# Strombegrenzung_RevA.net
KiCad netlist of a schematic drawn in EAGLE
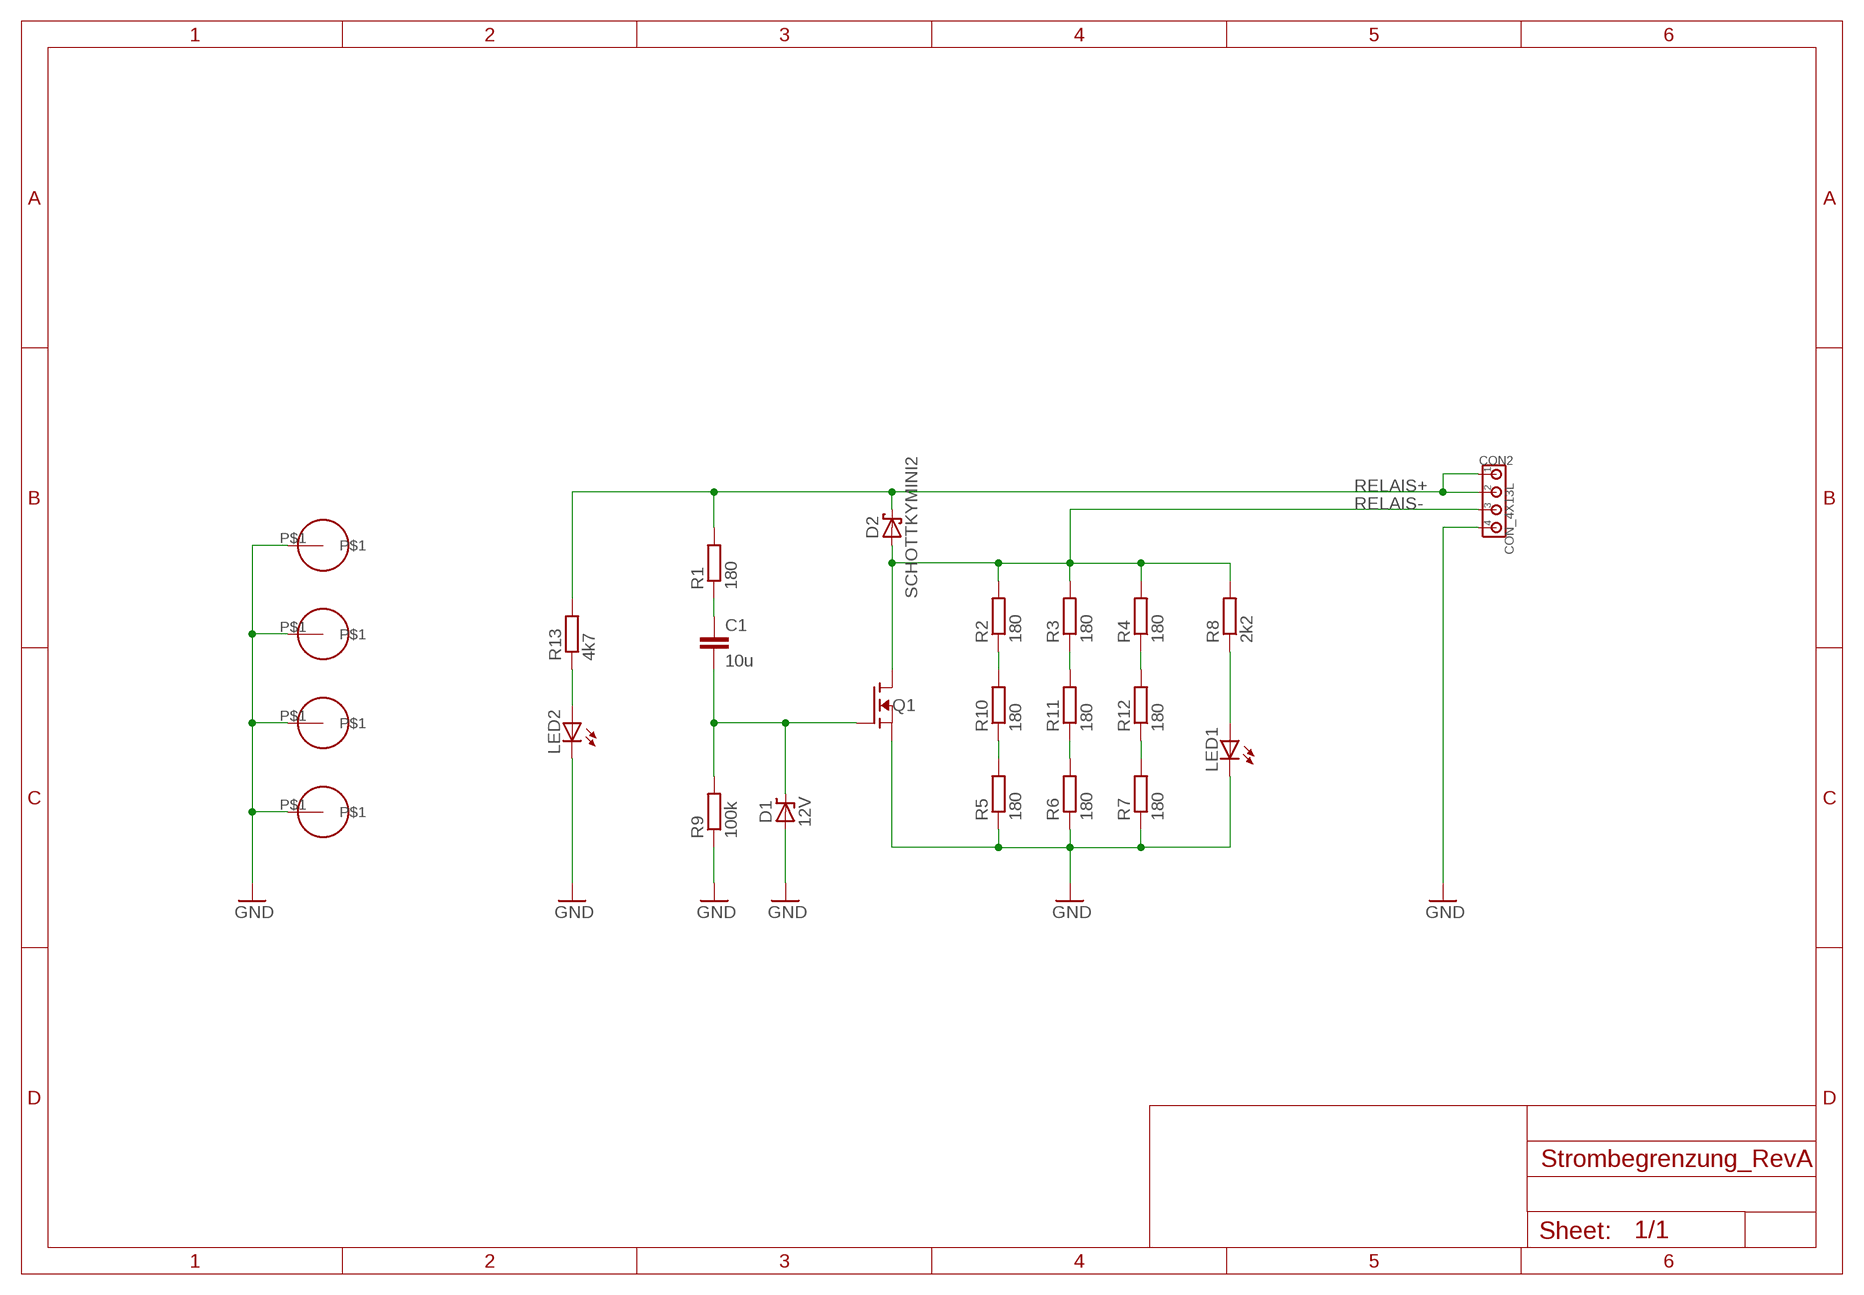
[diagram p0: schematic, sheet 1]

(export (version "E")
  (design (tool "Eeschema 10.0.6"))
  (components
    (comp (ref "C1")
      (value "10u")
      (footprint "eagle-import:C1206")
      (libsource (lib "eagle-import") (part "CC1206"))
    )
    (comp (ref "CON2")
      (value "CON_4X13L")
      (footprint "eagle-import:200MIL_4X")
      (libsource (lib "eagle-import") (part "CON_4X13L"))
    )
    (comp (ref "D1")
      (value "12V")
      (footprint "eagle-import:SOD323")
      (libsource (lib "eagle-import") (part "ZENERSOD323"))
    )
    (comp (ref "D2")
      (value "SCHOTTKYMINI2")
      (footprint "eagle-import:MINI2-F3-B")
      (libsource (lib "eagle-import") (part "SCHOTTKYMINI2"))
    )
    (comp (ref "LED1")
      (value "LED0805")
      (footprint "eagle-import:LED0805")
      (libsource (lib "eagle-import") (part "LED0805"))
    )
    (comp (ref "LED2")
      (value "LED0805")
      (footprint "eagle-import:LED0805")
      (libsource (lib "eagle-import") (part "LED0805"))
    )
    (comp (ref "Q1")
      (value "N-FETSOT23")
      (footprint "eagle-import:SOT23")
      (libsource (lib "eagle-import") (part "N-FETSOT23"))
    )
    (comp (ref "R1")
      (value "180")
      (footprint "eagle-import:R0805")
      (libsource (lib "eagle-import") (part "RESISTORR0805"))
    )
    (comp (ref "R2")
      (value "180")
      (footprint "eagle-import:R0805")
      (libsource (lib "eagle-import") (part "RESISTORR0805"))
    )
    (comp (ref "R3")
      (value "180")
      (footprint "eagle-import:R0805")
      (libsource (lib "eagle-import") (part "RESISTORR0805"))
    )
    (comp (ref "R4")
      (value "180")
      (footprint "eagle-import:R0805")
      (libsource (lib "eagle-import") (part "RESISTORR0805"))
    )
    (comp (ref "R5")
      (value "180")
      (footprint "eagle-import:R0805")
      (libsource (lib "eagle-import") (part "RESISTORR0805"))
    )
    (comp (ref "R6")
      (value "180")
      (footprint "eagle-import:R0805")
      (libsource (lib "eagle-import") (part "RESISTORR0805"))
    )
    (comp (ref "R7")
      (value "180")
      (footprint "eagle-import:R0805")
      (libsource (lib "eagle-import") (part "RESISTORR0805"))
    )
    (comp (ref "R8")
      (value "2k2")
      (footprint "eagle-import:R0805")
      (libsource (lib "eagle-import") (part "RESISTORR0805"))
    )
    (comp (ref "R9")
      (value "100k")
      (footprint "eagle-import:R0805")
      (libsource (lib "eagle-import") (part "RESISTORR0805"))
    )
    (comp (ref "R10")
      (value "180")
      (footprint "eagle-import:R0805")
      (libsource (lib "eagle-import") (part "RESISTORR0805"))
    )
    (comp (ref "R11")
      (value "180")
      (footprint "eagle-import:R0805")
      (libsource (lib "eagle-import") (part "RESISTORR0805"))
    )
    (comp (ref "R12")
      (value "180")
      (footprint "eagle-import:R0805")
      (libsource (lib "eagle-import") (part "RESISTORR0805"))
    )
    (comp (ref "R13")
      (value "4k7")
      (footprint "eagle-import:R0805")
      (libsource (lib "eagle-import") (part "RESISTORR0805"))
    )
    (comp (ref "U$1")
      (value "HOLE_3.3MM")
      (footprint "eagle-import:HOLE_3.3MM")
      (libsource (lib "eagle-import") (part "HOLE_3.3MM"))
    )
    (comp (ref "U$2")
      (value "HOLE_3.3MM")
      (footprint "eagle-import:HOLE_3.3MM")
      (libsource (lib "eagle-import") (part "HOLE_3.3MM"))
    )
    (comp (ref "U$3")
      (value "HOLE_3.3MM")
      (footprint "eagle-import:HOLE_3.3MM")
      (libsource (lib "eagle-import") (part "HOLE_3.3MM"))
    )
    (comp (ref "U$4")
      (value "HOLE_3.3MM")
      (footprint "eagle-import:HOLE_3.3MM")
      (libsource (lib "eagle-import") (part "HOLE_3.3MM"))
    )
  )
  (nets
    (net (code "1") (name "/RELAIS+") (class "Default")
      (node (ref "CON2") (pin "1") (pinfunction "1_1") (pintype "passive"))
      (node (ref "CON2") (pin "2") (pinfunction "2_2") (pintype "passive"))
      (node (ref "D2") (pin "C") (pinfunction "C_C") (pintype "passive"))
      (node (ref "R1") (pin "2") (pinfunction "2_2") (pintype "passive"))
      (node (ref "R13") (pin "2") (pinfunction "2_2") (pintype "passive"))
    )
    (net (code "2") (name "/RELAIS-") (class "Default")
      (node (ref "CON2") (pin "3") (pinfunction "3_3") (pintype "passive"))
      (node (ref "D2") (pin "A") (pinfunction "A_A") (pintype "passive"))
      (node (ref "Q1") (pin "3") (pinfunction "D_3") (pintype "passive"))
      (node (ref "R2") (pin "2") (pinfunction "2_2") (pintype "passive"))
      (node (ref "R3") (pin "2") (pinfunction "2_2") (pintype "passive"))
      (node (ref "R4") (pin "2") (pinfunction "2_2") (pintype "passive"))
      (node (ref "R8") (pin "2") (pinfunction "2_2") (pintype "passive"))
    )
    (net (code "3") (name "GND") (class "Default")
      (node (ref "CON2") (pin "4") (pinfunction "4_4") (pintype "passive"))
      (node (ref "D1") (pin "A") (pinfunction "A_A") (pintype "passive"))
      (node (ref "LED1") (pin "C") (pinfunction "C_C") (pintype "passive"))
      (node (ref "LED2") (pin "C") (pinfunction "C_C") (pintype "passive"))
      (node (ref "Q1") (pin "2") (pinfunction "S_2") (pintype "passive"))
      (node (ref "R5") (pin "1") (pinfunction "1_1") (pintype "passive"))
      (node (ref "R6") (pin "1") (pinfunction "1_1") (pintype "passive"))
      (node (ref "R7") (pin "1") (pinfunction "1_1") (pintype "passive"))
      (node (ref "R9") (pin "1") (pinfunction "1_1") (pintype "passive"))
      (node (ref "U$1") (pin "P$1") (pinfunction "P$1_P$1") (pintype "bidirectional"))
      (node (ref "U$2") (pin "P$1") (pinfunction "P$1_P$1") (pintype "bidirectional"))
      (node (ref "U$3") (pin "P$1") (pinfunction "P$1_P$1") (pintype "bidirectional"))
      (node (ref "U$4") (pin "P$1") (pinfunction "P$1_P$1") (pintype "bidirectional"))
    )
    (net (code "4") (name "Net-(C1-Pad1)") (class "Default")
      (node (ref "C1") (pin "1") (pinfunction "1_1") (pintype "passive"))
      (node (ref "R1") (pin "1") (pinfunction "1_1") (pintype "passive"))
    )
    (net (code "5") (name "Net-(LED1-PadA)") (class "Default")
      (node (ref "LED1") (pin "A") (pinfunction "A_A") (pintype "passive"))
      (node (ref "R8") (pin "1") (pinfunction "1_1") (pintype "passive"))
    )
    (net (code "6") (name "Net-(LED2-PadA)") (class "Default")
      (node (ref "LED2") (pin "A") (pinfunction "A_A") (pintype "passive"))
      (node (ref "R13") (pin "1") (pinfunction "1_1") (pintype "passive"))
    )
    (net (code "7") (name "Net-(Q1-G)") (class "Default")
      (node (ref "C1") (pin "2") (pinfunction "2_2") (pintype "passive"))
      (node (ref "D1") (pin "C") (pinfunction "C_C") (pintype "passive"))
      (node (ref "Q1") (pin "1") (pinfunction "G_1") (pintype "passive"))
      (node (ref "R9") (pin "2") (pinfunction "2_2") (pintype "passive"))
    )
    (net (code "8") (name "Net-(R10-Pad1)") (class "Default")
      (node (ref "R10") (pin "1") (pinfunction "1_1") (pintype "passive"))
      (node (ref "R5") (pin "2") (pinfunction "2_2") (pintype "passive"))
    )
    (net (code "9") (name "Net-(R10-Pad2)") (class "Default")
      (node (ref "R10") (pin "2") (pinfunction "2_2") (pintype "passive"))
      (node (ref "R2") (pin "1") (pinfunction "1_1") (pintype "passive"))
    )
    (net (code "10") (name "Net-(R11-Pad1)") (class "Default")
      (node (ref "R11") (pin "1") (pinfunction "1_1") (pintype "passive"))
      (node (ref "R6") (pin "2") (pinfunction "2_2") (pintype "passive"))
    )
    (net (code "11") (name "Net-(R11-Pad2)") (class "Default")
      (node (ref "R11") (pin "2") (pinfunction "2_2") (pintype "passive"))
      (node (ref "R3") (pin "1") (pinfunction "1_1") (pintype "passive"))
    )
    (net (code "12") (name "Net-(R12-Pad1)") (class "Default")
      (node (ref "R12") (pin "1") (pinfunction "1_1") (pintype "passive"))
      (node (ref "R7") (pin "2") (pinfunction "2_2") (pintype "passive"))
    )
    (net (code "13") (name "Net-(R12-Pad2)") (class "Default")
      (node (ref "R12") (pin "2") (pinfunction "2_2") (pintype "passive"))
      (node (ref "R4") (pin "1") (pinfunction "1_1") (pintype "passive"))
    )
  )
)
